# wenya.net
KiCad netlist of a schematic drawn in Altium Designer
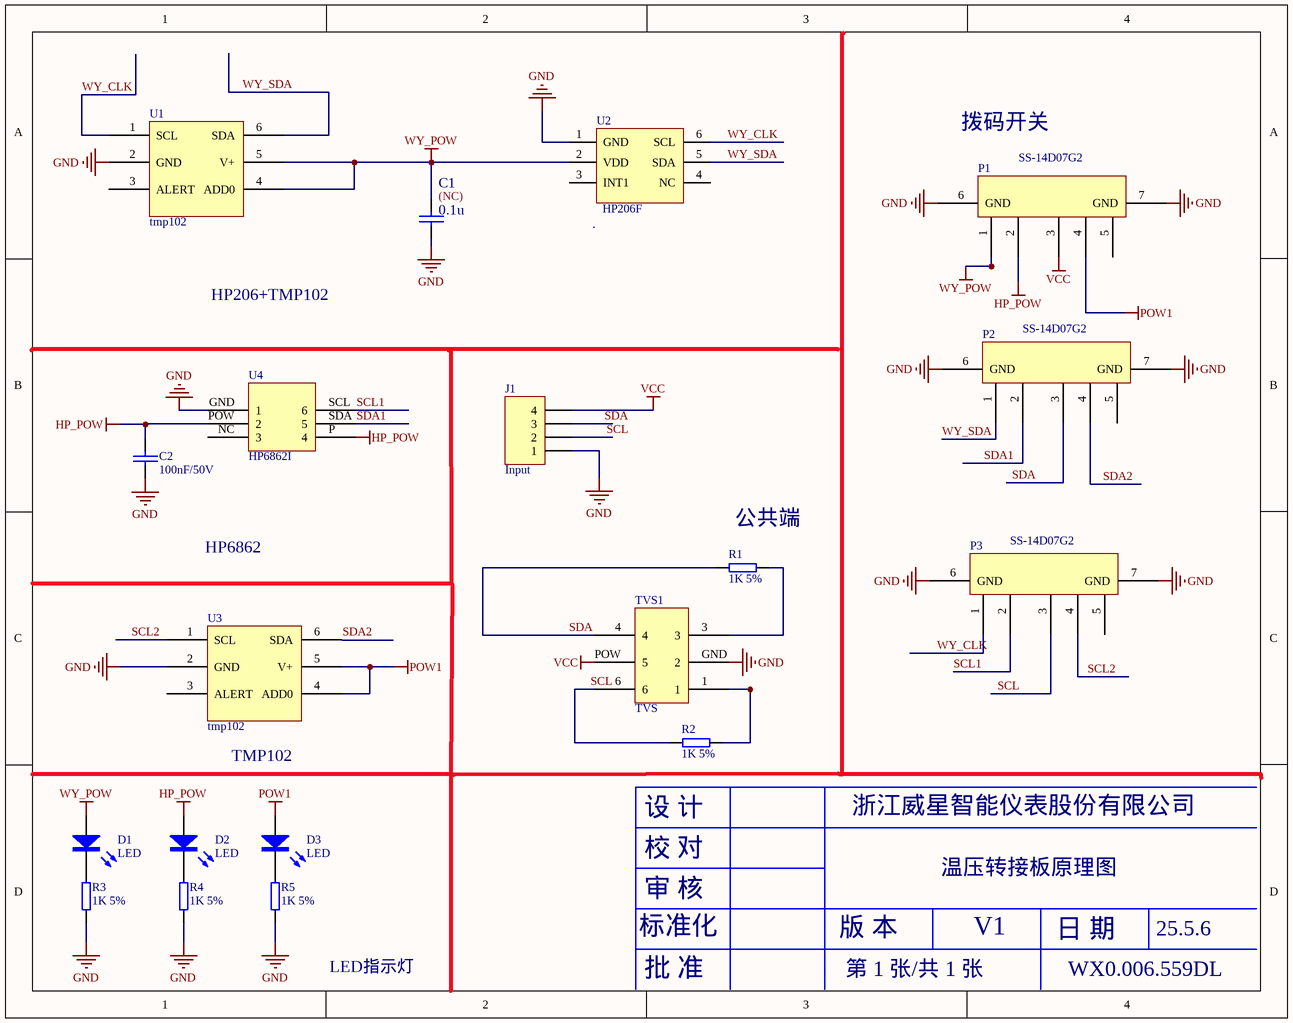
[diagram p0: wenya.SchDoc]

(export (version "E")
  (design (tool "Eeschema 10.0.6"))
  (components
    (comp (ref "C1")
      (value "0.1u")
      (footprint "C0603")
      (description "Capacitor")
      (libsource (lib "*") (part "CAP"))
    )
    (comp (ref "C2")
      (value "100nF/50V")
      (footprint "CAP0603")
      (description "104pF,50 V,±10%,0603,国巨,CC0603KRX7R9BB104")
      (fields (field (name "PART NUMBER") "101020103-0021"))
      (libsource (lib "Database_Libs2") (part "CC03K7R9_100N"))
    )
    (comp (ref "D1")
      (value "LED")
      (footprint "LED2_300")
      (description "圆形插件,3mm 圆形,插件,红光,湖北匡通电子有限公司,3BB4HC")
      (fields (field (name "PART NUMBER") "101040102-0001"))
      (libsource (lib "Database_Libs2") (part "01-LED_T3R"))
    )
    (comp (ref "D2")
      (value "LED")
      (footprint "LED2_300")
      (description "圆形插件,3mm 圆形,插件,红光,湖北匡通电子有限公司,3BB4HC")
      (fields (field (name "PART NUMBER") "101040102-0001"))
      (libsource (lib "Database_Libs2") (part "01-LED_T3R"))
    )
    (comp (ref "D3")
      (value "LED")
      (footprint "LED2_300")
      (description "圆形插件,3mm 圆形,插件,红光,湖北匡通电子有限公司,3BB4HC")
      (fields (field (name "PART NUMBER") "101040102-0001"))
      (libsource (lib "Database_Libs2") (part "01-LED_T3R"))
    )
    (comp (ref "J1")
      (value "Input")
      (footprint "HDR1X4")
      (description "Header, 4-Pin")
      (libsource (lib "CBB_Lib_SCH") (part "Header 4"))
    )
    (comp (ref "P1")
      (value "SS-14D07G2")
      (footprint "PCBComponent_1 - duplicate")
      (libsource (lib "Schlib1") (part "SS-14D07G2"))
    )
    (comp (ref "P2")
      (value "SS-14D07G2")
      (footprint "PCBComponent_1 - duplicate")
      (libsource (lib "Schlib1") (part "SS-14D07G2"))
    )
    (comp (ref "P3")
      (value "SS-14D07G2")
      (footprint "PCBComponent_1 - duplicate")
      (libsource (lib "Schlib1") (part "SS-14D07G2"))
    )
    (comp (ref "R1")
      (value "1K 5%")
      (footprint "RES0603")
      (description "1K,±5%,1/10W,0603,国巨,RC0603JR-071KL")
      (fields (field (name "PART NUMBER") "101010103-0008"))
      (libsource (lib "Database_Libs2") (part "RC03J_1K"))
    )
    (comp (ref "R2")
      (value "1K 5%")
      (footprint "RES0603")
      (description "1K,±5%,1/10W,0603,国巨,RC0603JR-071KL")
      (fields (field (name "PART NUMBER") "101010103-0008"))
      (libsource (lib "Database_Libs2") (part "RC03J_1K"))
    )
    (comp (ref "R3")
      (value "1K 5%")
      (footprint "RES0603")
      (description "1K,±5%,1/10W,0603,国巨,RC0603JR-071KL")
      (fields (field (name "PART NUMBER") "101010103-0008"))
      (libsource (lib "Database_Libs2") (part "RC03J_1K"))
    )
    (comp (ref "R4")
      (value "1K 5%")
      (footprint "RES0603")
      (description "1K,±5%,1/10W,0603,国巨,RC0603JR-071KL")
      (fields (field (name "PART NUMBER") "101010103-0008"))
      (libsource (lib "Database_Libs2") (part "RC03J_1K"))
    )
    (comp (ref "R5")
      (value "1K 5%")
      (footprint "RES0603")
      (description "1K,±5%,1/10W,0603,国巨,RC0603JR-071KL")
      (fields (field (name "PART NUMBER") "101010103-0008"))
      (libsource (lib "Database_Libs2") (part "RC03J_1K"))
    )
    (comp (ref "TVS1") (value "TVS") (footprint "ESD") (libsource (lib "Schlib1") (part "TVS")))
    (comp (ref "U1") (value "tmp102") (footprint "SO-P6") (libsource (lib "chip") (part "tem102")))
    (comp (ref "U2") (value ".") (footprint "HP206C") (libsource (lib "chip") (part "HP206C")))
    (comp (ref "U3") (value "tmp102") (footprint "SO-P6") (libsource (lib "chip") (part "tem102")))
    (comp (ref "U4") (value "HP6862I") (footprint "huapu") (libsource (lib "Schlib1") (part "HP6862I")))
  )
  (nets
    (net (code "1") (name "/SCL") (class "Default")
      (node (ref "J1") (pin "2") (pinfunction "2_2") (pintype "passive"))
      (node (ref "P3") (pin "3") (pintype "passive"))
      (node (ref "R2") (pin "2") (pinfunction "2_2") (pintype "passive"))
      (node (ref "TVS1") (pin "6") (pinfunction "6_6") (pintype "passive"))
    )
    (net (code "2") (name "/SCL1") (class "Default")
      (node (ref "P3") (pin "2") (pintype "passive"))
      (node (ref "U4") (pin "SCL") (pinfunction "6_SCL") (pintype "passive"))
    )
    (net (code "3") (name "/SCL2") (class "Default")
      (node (ref "P3") (pin "4") (pintype "passive"))
      (node (ref "U3") (pin "1") (pinfunction "SCL_1") (pintype "passive"))
    )
    (net (code "4") (name "/SDA") (class "Default")
      (node (ref "J1") (pin "3") (pinfunction "3_3") (pintype "passive"))
      (node (ref "P2") (pin "3") (pintype "passive"))
      (node (ref "R1") (pin "2") (pinfunction "2_2") (pintype "passive"))
      (node (ref "TVS1") (pin "4") (pinfunction "4_4") (pintype "passive"))
    )
    (net (code "5") (name "/SDA1") (class "Default")
      (node (ref "P2") (pin "2") (pintype "passive"))
      (node (ref "U4") (pin "SDA") (pinfunction "5_SDA") (pintype "passive"))
    )
    (net (code "6") (name "/SDA2") (class "Default")
      (node (ref "P2") (pin "4") (pintype "passive"))
      (node (ref "U3") (pin "6") (pinfunction "SDA_6") (pintype "passive"))
    )
    (net (code "7") (name "/WY_CLK") (class "Default")
      (node (ref "P3") (pin "1") (pintype "passive"))
      (node (ref "U1") (pin "1") (pinfunction "SCL_1") (pintype "passive"))
      (node (ref "U2") (pin "6") (pinfunction "SCL_6") (pintype "passive"))
    )
    (net (code "8") (name "/WY_SDA") (class "Default")
      (node (ref "P2") (pin "1") (pintype "passive"))
      (node (ref "U1") (pin "6") (pinfunction "SDA_6") (pintype "passive"))
      (node (ref "U2") (pin "5") (pinfunction "SDA_5") (pintype "passive"))
    )
    (net (code "9") (name "GND") (class "Default")
      (node (ref "C1") (pin "2") (pinfunction "2_2") (pintype "passive"))
      (node (ref "C2") (pin "1") (pinfunction "1_1") (pintype "passive"))
      (node (ref "J1") (pin "1") (pinfunction "1_1") (pintype "passive"))
      (node (ref "P1") (pin "6") (pinfunction "GND_6") (pintype "passive"))
      (node (ref "P1") (pin "7") (pinfunction "GND_7") (pintype "passive"))
      (node (ref "P2") (pin "6") (pinfunction "GND_6") (pintype "passive"))
      (node (ref "P2") (pin "7") (pinfunction "GND_7") (pintype "passive"))
      (node (ref "P3") (pin "6") (pinfunction "GND_6") (pintype "passive"))
      (node (ref "P3") (pin "7") (pinfunction "GND_7") (pintype "passive"))
      (node (ref "R3") (pin "2") (pinfunction "2_2") (pintype "passive"))
      (node (ref "R4") (pin "2") (pinfunction "2_2") (pintype "passive"))
      (node (ref "R5") (pin "2") (pinfunction "2_2") (pintype "passive"))
      (node (ref "TVS1") (pin "GND") (pinfunction "2_GND") (pintype "passive"))
      (node (ref "U1") (pin "2") (pinfunction "GND_2") (pintype "passive"))
      (node (ref "U2") (pin "1") (pinfunction "GND_1") (pintype "passive"))
      (node (ref "U3") (pin "2") (pinfunction "GND_2") (pintype "passive"))
      (node (ref "U4") (pin "GND") (pinfunction "1_GND") (pintype "passive"))
    )
    (net (code "10") (name "HP_POW") (class "Default")
      (node (ref "C2") (pin "2") (pinfunction "2_2") (pintype "passive"))
      (node (ref "D2") (pin "1") (pinfunction "1_1") (pintype "passive"))
      (node (ref "P1") (pin "2") (pintype "passive"))
      (node (ref "U4") (pin "P") (pinfunction "4_P") (pintype "passive"))
      (node (ref "U4") (pin "POW") (pinfunction "2_POW") (pintype "passive"))
    )
    (net (code "11") (name "Net-(D1-Pad2)") (class "Default")
      (node (ref "D1") (pin "2") (pinfunction "2_2") (pintype "passive"))
      (node (ref "R3") (pin "1") (pinfunction "1_1") (pintype "passive"))
    )
    (net (code "12") (name "Net-(D2-Pad2)") (class "Default")
      (node (ref "D2") (pin "2") (pinfunction "2_2") (pintype "passive"))
      (node (ref "R4") (pin "1") (pinfunction "1_1") (pintype "passive"))
    )
    (net (code "13") (name "Net-(D3-Pad2)") (class "Default")
      (node (ref "D3") (pin "2") (pinfunction "2_2") (pintype "passive"))
      (node (ref "R5") (pin "1") (pinfunction "1_1") (pintype "passive"))
    )
    (net (code "14") (name "Net-(R1-Pad1)") (class "Default")
      (node (ref "R1") (pin "1") (pinfunction "1_1") (pintype "passive"))
      (node (ref "TVS1") (pin "3") (pinfunction "3_3") (pintype "passive"))
    )
    (net (code "15") (name "Net-(R2-Pad1)") (class "Default")
      (node (ref "R2") (pin "1") (pinfunction "1_1") (pintype "passive"))
      (node (ref "TVS1") (pin "1") (pinfunction "1_1") (pintype "passive"))
    )
    (net (code "16") (name "POW1") (class "Default")
      (node (ref "D3") (pin "1") (pinfunction "1_1") (pintype "passive"))
      (node (ref "P1") (pin "4") (pintype "passive"))
      (node (ref "U3") (pin "4") (pinfunction "ADD0_4") (pintype "passive"))
      (node (ref "U3") (pin "5") (pinfunction "V+_5") (pintype "passive"))
    )
    (net (code "17") (name "VCC") (class "Default")
      (node (ref "J1") (pin "4") (pinfunction "4_4") (pintype "passive"))
      (node (ref "P1") (pin "3") (pintype "passive"))
      (node (ref "TVS1") (pin "POW") (pinfunction "5_POW") (pintype "passive"))
    )
    (net (code "18") (name "WY_POW") (class "Default")
      (node (ref "C1") (pin "1") (pinfunction "1_1") (pintype "passive"))
      (node (ref "D1") (pin "1") (pinfunction "1_1") (pintype "passive"))
      (node (ref "P1") (pin "1") (pintype "passive"))
      (node (ref "U1") (pin "4") (pinfunction "ADD0_4") (pintype "passive"))
      (node (ref "U1") (pin "5") (pinfunction "V+_5") (pintype "passive"))
      (node (ref "U2") (pin "2") (pinfunction "VDD_2") (pintype "passive"))
    )
    (net (code "19") (name "unconnected-(P1-Pad5)") (class "Default")
      (node (ref "P1") (pin "5") (pintype "passive"))
    )
    (net (code "20") (name "unconnected-(P2-Pad5)") (class "Default")
      (node (ref "P2") (pin "5") (pintype "passive"))
    )
    (net (code "21") (name "unconnected-(P3-Pad5)") (class "Default")
      (node (ref "P3") (pin "5") (pintype "passive"))
    )
    (net (code "22") (name "unconnected-(U1-ALERT-Pad3)") (class "Default")
      (node (ref "U1") (pin "3") (pinfunction "ALERT_3") (pintype "passive"))
    )
    (net (code "23") (name "unconnected-(U2-INT1-Pad3)") (class "Default")
      (node (ref "U2") (pin "3") (pinfunction "INT1_3") (pintype "passive"))
    )
    (net (code "24") (name "unconnected-(U2-NC-Pad4)") (class "Default")
      (node (ref "U2") (pin "4") (pinfunction "NC_4") (pintype "passive"))
    )
    (net (code "25") (name "unconnected-(U3-ALERT-Pad3)") (class "Default")
      (node (ref "U3") (pin "3") (pinfunction "ALERT_3") (pintype "passive"))
    )
    (net (code "26") (name "unconnected-(U4-3-PadNC)") (class "Default")
      (node (ref "U4") (pin "NC") (pinfunction "3_NC") (pintype "passive"))
    )
  )
)
